# NAND.net
KiCad netlist of a schematic drawn in EAGLE
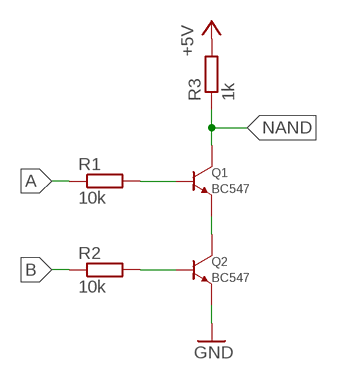
[diagram p0: schematic, sheet 1]

(export (version "E")
  (design (tool "Eeschema 10.0.6"))
  (components
    (comp (ref "Q1")
      (value "BC547")
      (footprint "eagle-import:SOT23")
      (libsource (lib "eagle-import") (part "TRANSISTOR-NPN-GENERIC-SOT23-BECDEFAULT"))
    )
    (comp (ref "Q2")
      (value "BC547")
      (footprint "eagle-import:SOT23")
      (libsource (lib "eagle-import") (part "TRANSISTOR-NPN-GENERIC-SOT23-BECDEFAULT"))
    )
    (comp (ref "R1")
      (value "10k")
      (footprint "eagle-import:R0603")
      (libsource (lib "eagle-import") (part "R-EU_R0603"))
    )
    (comp (ref "R2")
      (value "10k")
      (footprint "eagle-import:R0603")
      (libsource (lib "eagle-import") (part "R-EU_R0603"))
    )
    (comp (ref "R3")
      (value "1k")
      (footprint "eagle-import:R0603")
      (libsource (lib "eagle-import") (part "R-EU_R0603"))
    )
  )
  (nets
    (net (code "1") (name "+5V") (class "Default")
      (node (ref "R3") (pin "2") (pinfunction "2_2") (pintype "passive"))
    )
    (net (code "2") (name "A") (class "Default")
      (node (ref "R1") (pin "1") (pinfunction "1_1") (pintype "passive"))
    )
    (net (code "3") (name "B") (class "Default")
      (node (ref "R2") (pin "1") (pinfunction "1_1") (pintype "passive"))
    )
    (net (code "4") (name "GND") (class "Default")
      (node (ref "Q2") (pin "P$2") (pinfunction "EMITTER_P$2") (pintype "bidirectional"))
    )
    (net (code "5") (name "NAND") (class "Default")
      (node (ref "Q1") (pin "P$3") (pinfunction "COLLECTOR_P$3") (pintype "bidirectional"))
      (node (ref "R3") (pin "1") (pinfunction "1_1") (pintype "passive"))
    )
    (net (code "6") (name "Net-(Q1-BASE)") (class "Default")
      (node (ref "Q1") (pin "P$1") (pinfunction "BASE_P$1") (pintype "bidirectional"))
      (node (ref "R1") (pin "2") (pinfunction "2_2") (pintype "passive"))
    )
    (net (code "7") (name "Net-(Q1-EMITTER)") (class "Default")
      (node (ref "Q1") (pin "P$2") (pinfunction "EMITTER_P$2") (pintype "bidirectional"))
      (node (ref "Q2") (pin "P$3") (pinfunction "COLLECTOR_P$3") (pintype "bidirectional"))
    )
    (net (code "8") (name "Net-(Q2-BASE)") (class "Default")
      (node (ref "Q2") (pin "P$1") (pinfunction "BASE_P$1") (pintype "bidirectional"))
      (node (ref "R2") (pin "2") (pinfunction "2_2") (pintype "passive"))
    )
  )
)
